# Plugs.net
KiCad netlist of a schematic drawn in Altium Designer
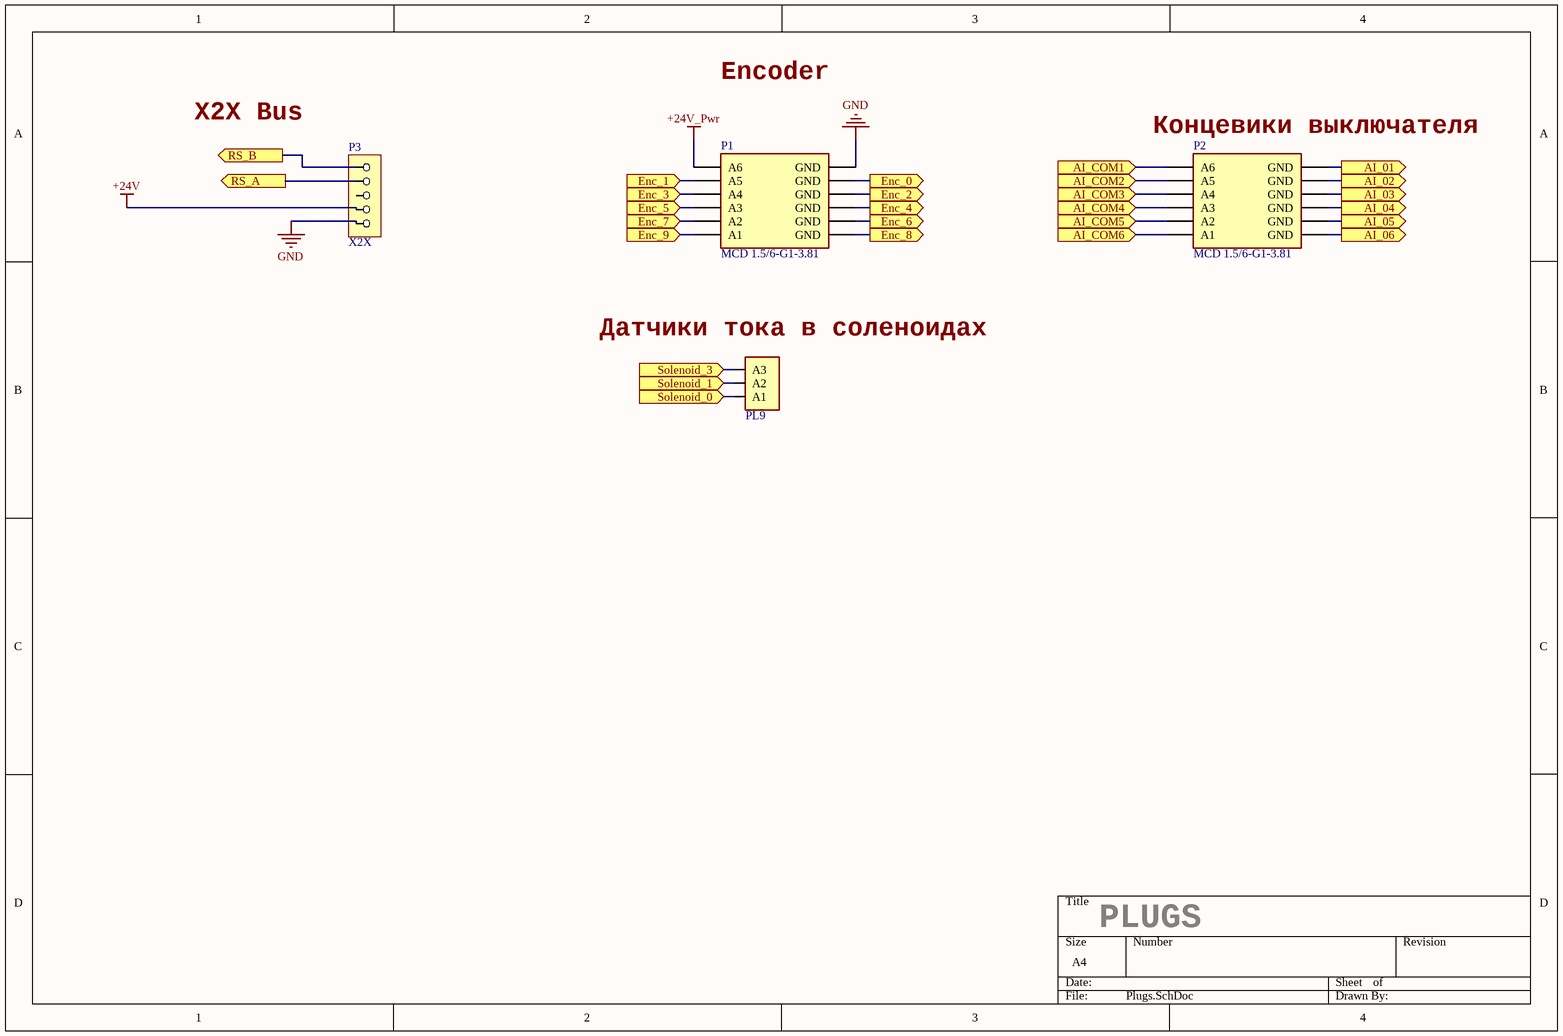
[diagram p0: Plugs.SchDoc]

(export (version "E")
  (design (tool "Eeschema 10.0.6"))
  (components
    (comp (ref "P1")
      (value "MCD 1.5/6-G1-3.81")
      (footprint "PcbLib1:mcd 1,5/6-G1-3.81")
      (description "Header, 6-Pin, Dual row")
      (fields (field (name "PUBLISHER") "Altium Limited"))
      (libsource (lib "kontr") (part "Header 6X2"))
    )
    (comp (ref "P2")
      (value "MCD 1.5/6-G1-3.81")
      (footprint "PcbLib1:mcd 1,5/6-G1-3.81")
      (description "Header, 6-Pin, Dual row")
      (fields (field (name "PUBLISHER") "Altium Limited"))
      (libsource (lib "kontr") (part "Header 6X2"))
    )
    (comp (ref "P3")
      (value "X2X")
      (footprint "PhClass5")
      (description "EMSTBA 2.5/5-G-5.08")
      (libsource (lib "kontr") (part "EMSTBA 2.5/5-G-5.08"))
    )
    (comp (ref "PL9")
      (value "Plug 3Pin")
      (footprint "3.81 Plug")
      (description "15EDGRC-3.81-03P-14-00AH")
      (libsource (lib "kontr") (part "Plug 3Pin"))
    )
  )
  (nets
    (net (code "1") (name "+24V") (class "Default")
      (node (ref "P3") (pin "4") (pinfunction "2_4") (pintype "passive"))
    )
    (net (code "2") (name "+24V_Pwr") (class "Default")
      (node (ref "P1") (pin "1") (pinfunction "A6_1") (pintype "passive"))
    )
    (net (code "3") (name "/AI_01") (class "Default")
      (node (ref "P2") (pin "2") (pinfunction "GND_2") (pintype "passive"))
    )
    (net (code "4") (name "/AI_02") (class "Default")
      (node (ref "P2") (pin "4") (pinfunction "GND_4") (pintype "passive"))
    )
    (net (code "5") (name "/AI_03") (class "Default")
      (node (ref "P2") (pin "6") (pinfunction "GND_6") (pintype "passive"))
    )
    (net (code "6") (name "/AI_04") (class "Default")
      (node (ref "P2") (pin "8") (pinfunction "GND_8") (pintype "passive"))
    )
    (net (code "7") (name "/AI_05") (class "Default")
      (node (ref "P2") (pin "10") (pinfunction "GND_10") (pintype "passive"))
    )
    (net (code "8") (name "/AI_06") (class "Default")
      (node (ref "P2") (pin "12") (pinfunction "GND_12") (pintype "passive"))
    )
    (net (code "9") (name "/AI_COM1") (class "Default")
      (node (ref "P2") (pin "1") (pinfunction "A6_1") (pintype "passive"))
    )
    (net (code "10") (name "/AI_COM2") (class "Default")
      (node (ref "P2") (pin "3") (pinfunction "A5_3") (pintype "passive"))
    )
    (net (code "11") (name "/AI_COM3") (class "Default")
      (node (ref "P2") (pin "5") (pinfunction "A4_5") (pintype "passive"))
    )
    (net (code "12") (name "/AI_COM4") (class "Default")
      (node (ref "P2") (pin "7") (pinfunction "A3_7") (pintype "passive"))
    )
    (net (code "13") (name "/AI_COM5") (class "Default")
      (node (ref "P2") (pin "9") (pinfunction "A2_9") (pintype "passive"))
    )
    (net (code "14") (name "/AI_COM6") (class "Default")
      (node (ref "P2") (pin "11") (pinfunction "A1_11") (pintype "passive"))
    )
    (net (code "15") (name "/Enc_0") (class "Default")
      (node (ref "P1") (pin "4") (pinfunction "GND_4") (pintype "passive"))
    )
    (net (code "16") (name "/Enc_1") (class "Default")
      (node (ref "P1") (pin "3") (pinfunction "A5_3") (pintype "passive"))
    )
    (net (code "17") (name "/Enc_2") (class "Default")
      (node (ref "P1") (pin "6") (pinfunction "GND_6") (pintype "passive"))
    )
    (net (code "18") (name "/Enc_3") (class "Default")
      (node (ref "P1") (pin "5") (pinfunction "A4_5") (pintype "passive"))
    )
    (net (code "19") (name "/Enc_4") (class "Default")
      (node (ref "P1") (pin "8") (pinfunction "GND_8") (pintype "passive"))
    )
    (net (code "20") (name "/Enc_5") (class "Default")
      (node (ref "P1") (pin "7") (pinfunction "A3_7") (pintype "passive"))
    )
    (net (code "21") (name "/Enc_6") (class "Default")
      (node (ref "P1") (pin "10") (pinfunction "GND_10") (pintype "passive"))
    )
    (net (code "22") (name "/Enc_7") (class "Default")
      (node (ref "P1") (pin "9") (pinfunction "A2_9") (pintype "passive"))
    )
    (net (code "23") (name "/Enc_8") (class "Default")
      (node (ref "P1") (pin "12") (pinfunction "GND_12") (pintype "passive"))
    )
    (net (code "24") (name "/Enc_9") (class "Default")
      (node (ref "P1") (pin "11") (pinfunction "A1_11") (pintype "passive"))
    )
    (net (code "25") (name "/RS_A") (class "Default")
      (node (ref "P3") (pin "2") (pinfunction "2_2") (pintype "passive"))
    )
    (net (code "26") (name "/RS_B") (class "Default")
      (node (ref "P3") (pin "1") (pinfunction "1_1") (pintype "passive"))
    )
    (net (code "27") (name "/Solenoid_0") (class "Default")
      (node (ref "PL9") (pin "1") (pinfunction "A1_1") (pintype "passive"))
    )
    (net (code "28") (name "/Solenoid_1") (class "Default")
      (node (ref "PL9") (pin "2") (pinfunction "A2_2") (pintype "passive"))
    )
    (net (code "29") (name "/Solenoid_3") (class "Default")
      (node (ref "PL9") (pin "3") (pinfunction "A3_3") (pintype "passive"))
    )
    (net (code "30") (name "GND") (class "Default")
      (node (ref "P1") (pin "2") (pinfunction "GND_2") (pintype "passive"))
      (node (ref "P3") (pin "5") (pinfunction "3_5") (pintype "passive"))
    )
    (net (code "31") (name "unconnected-(P3-Pad3)") (class "Default")
      (node (ref "P3") (pin "3") (pinfunction "3_3") (pintype "passive"))
    )
  )
)
